# HUD.net
KiCad netlist of a schematic drawn in EAGLE
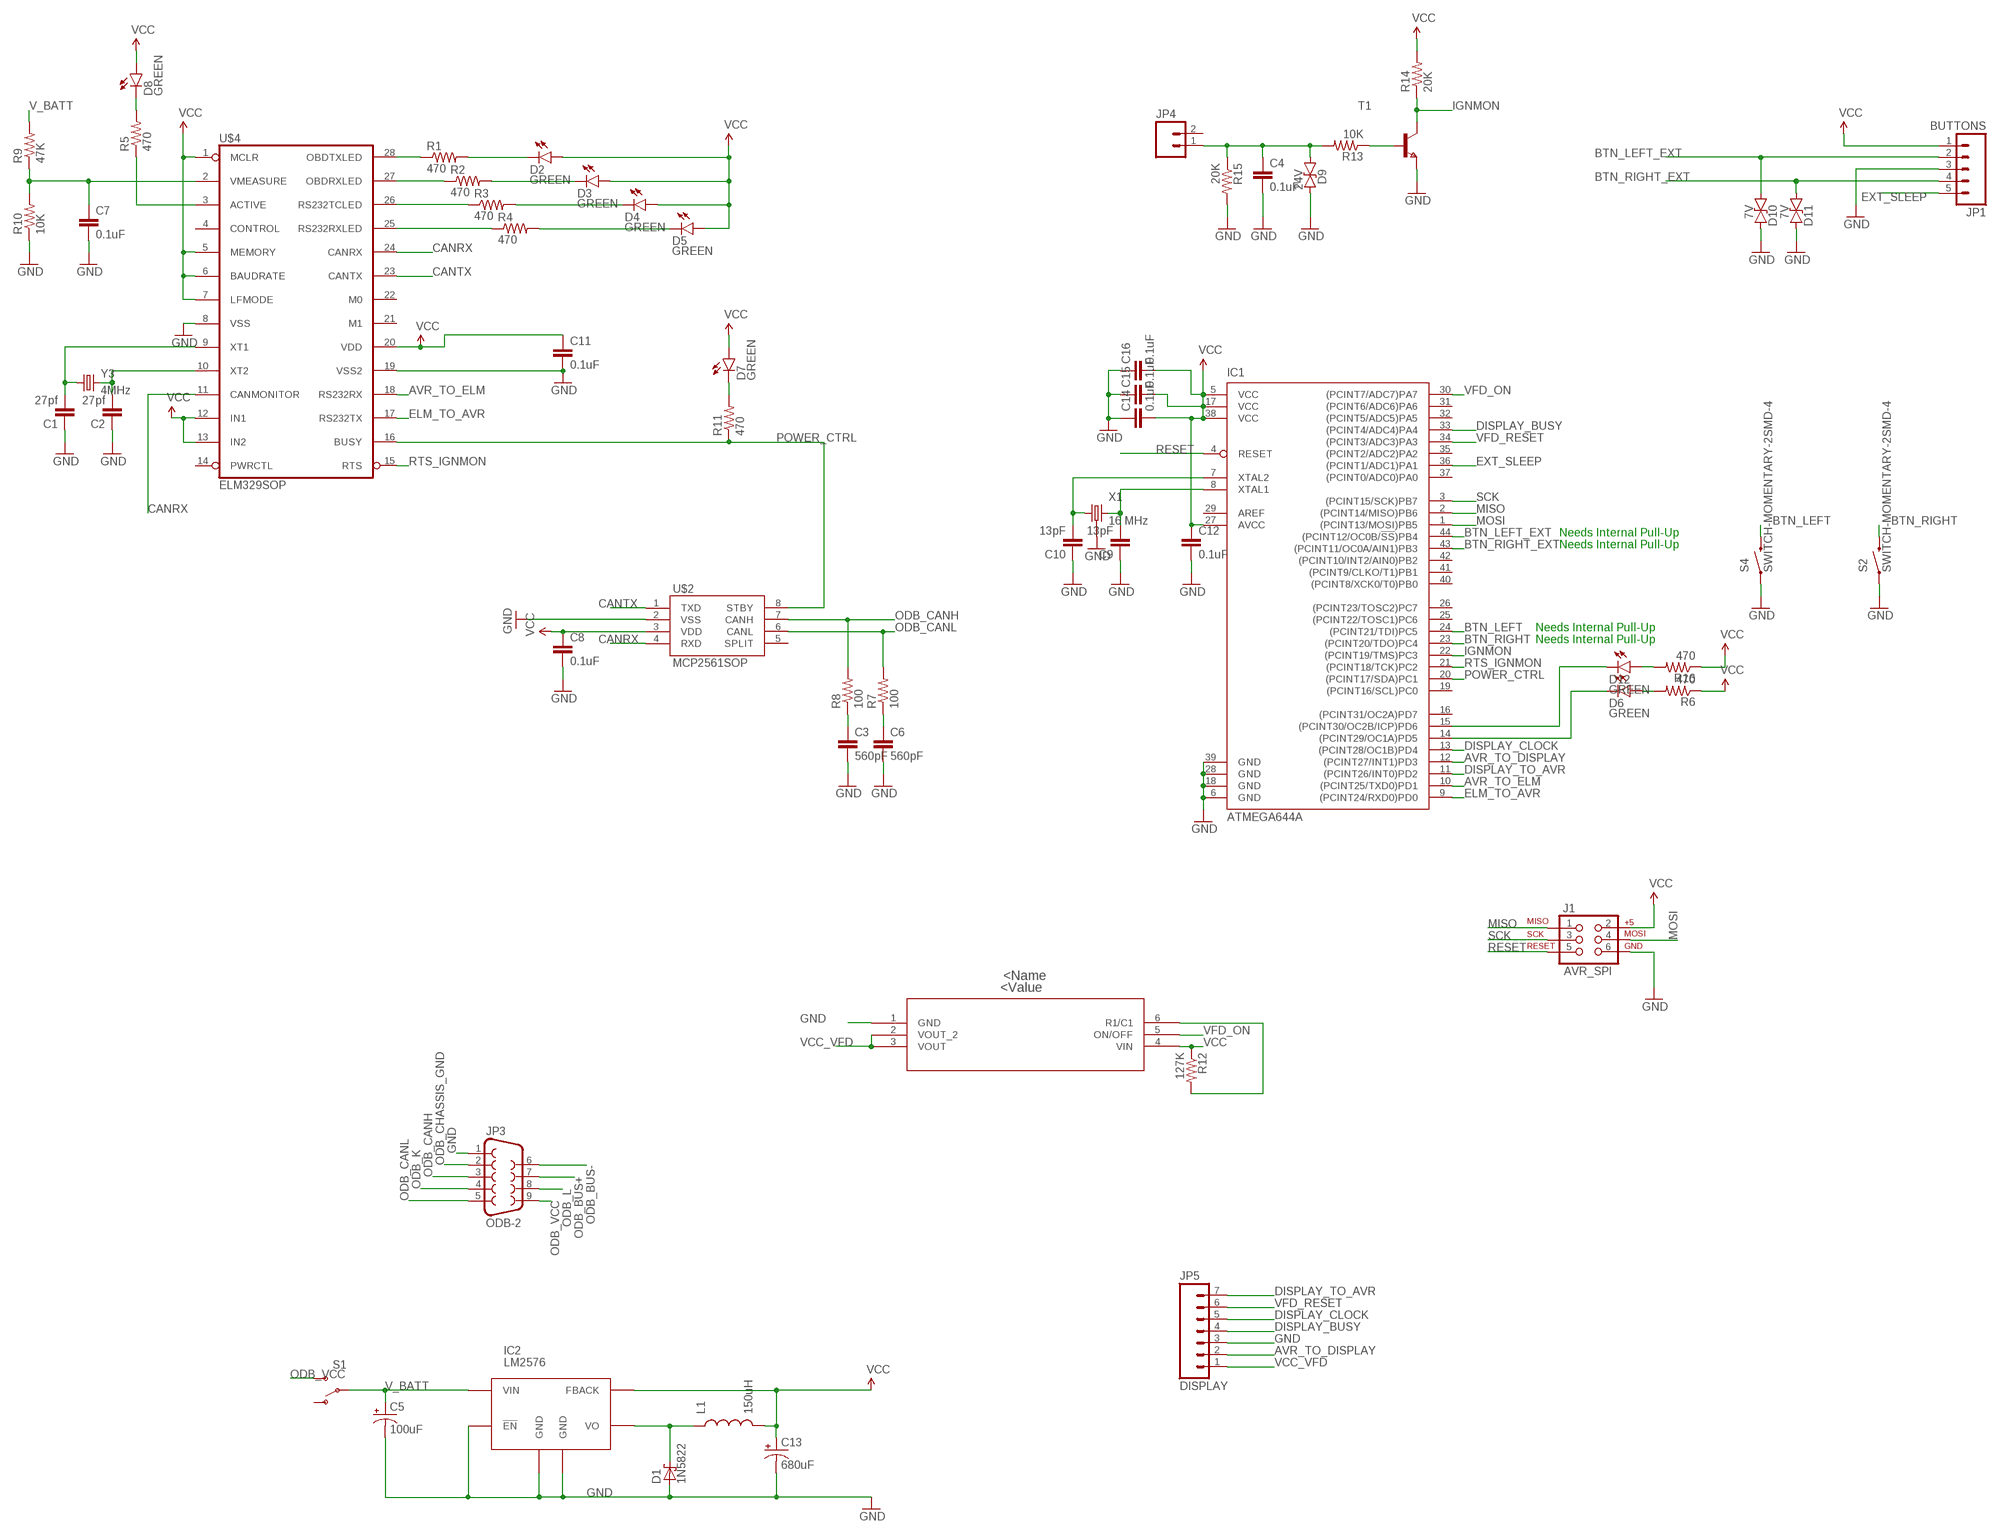
[diagram p0: schematic, sheet 1]

(export (version "E")
  (design (tool "Eeschema 10.0.6"))
  (components
    (comp (ref "C1")
      (value "27pf")
      (footprint "eagle-import:0603-CAP")
      (libsource (lib "eagle-import") (part "560PF-50V-5%(0603)"))
    )
    (comp (ref "C2")
      (value "27pf")
      (footprint "eagle-import:0603-CAP")
      (libsource (lib "eagle-import") (part "560PF-50V-5%(0603)"))
    )
    (comp (ref "C3")
      (value "560pF")
      (footprint "eagle-import:0603-CAP")
      (libsource (lib "eagle-import") (part "560PF-50V-5%(0603)"))
    )
    (comp (ref "C4")
      (value "0.1uF")
      (footprint "eagle-import:0603-CAP")
      (libsource (lib "eagle-import") (part "560PF-50V-5%(0603)"))
    )
    (comp (ref "C5")
      (value "100uF")
      (footprint "eagle-import:CPOL-RADIAL-100UF-25V")
      (libsource (lib "eagle-import") (part "CAP_POLPTH1"))
    )
    (comp (ref "C6")
      (value "560pF")
      (footprint "eagle-import:0603-CAP")
      (libsource (lib "eagle-import") (part "560PF-50V-5%(0603)"))
    )
    (comp (ref "C7")
      (value "0.1uF")
      (footprint "eagle-import:0603-CAP")
      (libsource (lib "eagle-import") (part "560PF-50V-5%(0603)"))
    )
    (comp (ref "C8")
      (value "0.1uF")
      (footprint "eagle-import:0603-CAP")
      (libsource (lib "eagle-import") (part "560PF-50V-5%(0603)"))
    )
    (comp (ref "C9")
      (value "13pF")
      (footprint "eagle-import:0603-CAP")
      (libsource (lib "eagle-import") (part "560PF-50V-5%(0603)"))
    )
    (comp (ref "C10")
      (value "13pF")
      (footprint "eagle-import:0603-CAP")
      (libsource (lib "eagle-import") (part "560PF-50V-5%(0603)"))
    )
    (comp (ref "C11")
      (value "0.1uF")
      (footprint "eagle-import:0603-CAP")
      (libsource (lib "eagle-import") (part "560PF-50V-5%(0603)"))
    )
    (comp (ref "C12")
      (value "0.1uF")
      (footprint "eagle-import:0603-CAP")
      (libsource (lib "eagle-import") (part "560PF-50V-5%(0603)"))
    )
    (comp (ref "C13")
      (value "680uF")
      (footprint "eagle-import:CPOL-RADIAL-1000UF-25V")
      (libsource (lib "eagle-import") (part "1000UF-25V(PTH)"))
    )
    (comp (ref "C14")
      (value "0.1uF")
      (footprint "eagle-import:0603-CAP")
      (libsource (lib "eagle-import") (part "560PF-50V-5%(0603)"))
    )
    (comp (ref "C15")
      (value "0.1uF")
      (footprint "eagle-import:0603-CAP")
      (libsource (lib "eagle-import") (part "560PF-50V-5%(0603)"))
    )
    (comp (ref "C16")
      (value "0.1uF")
      (footprint "eagle-import:0603-CAP")
      (libsource (lib "eagle-import") (part "560PF-50V-5%(0603)"))
    )
    (comp (ref "D1")
      (value "1N5822")
      (footprint "eagle-import:DO201T15")
      (libsource (lib "eagle-import") (part "SCHOTTKY-DIODEDO201T15"))
    )
    (comp (ref "D2")
      (value "GREEN")
      (footprint "eagle-import:LED-1206")
      (libsource (lib "eagle-import") (part "LED-GREENLARGE"))
    )
    (comp (ref "D3")
      (value "GREEN")
      (footprint "eagle-import:LED-1206")
      (libsource (lib "eagle-import") (part "LED-GREENLARGE"))
    )
    (comp (ref "D4")
      (value "GREEN")
      (footprint "eagle-import:LED-1206")
      (libsource (lib "eagle-import") (part "LED-GREENLARGE"))
    )
    (comp (ref "D5")
      (value "GREEN")
      (footprint "eagle-import:LED-1206")
      (libsource (lib "eagle-import") (part "LED-GREENLARGE"))
    )
    (comp (ref "D6")
      (value "GREEN")
      (footprint "eagle-import:LED-1206")
      (libsource (lib "eagle-import") (part "LED-GREENLARGE"))
    )
    (comp (ref "D7")
      (value "GREEN")
      (footprint "eagle-import:LED-1206")
      (libsource (lib "eagle-import") (part "LED-GREENLARGE"))
    )
    (comp (ref "D8")
      (value "GREEN")
      (footprint "eagle-import:LED-1206")
      (libsource (lib "eagle-import") (part "LED-GREENLARGE"))
    )
    (comp (ref "D9")
      (value "24V")
      (footprint "eagle-import:SOD-123")
      (libsource (lib "eagle-import") (part "DIODE-TVS16V"))
    )
    (comp (ref "D10")
      (value "7V")
      (footprint "eagle-import:SOD-123")
      (libsource (lib "eagle-import") (part "DIODE-TVS16V"))
    )
    (comp (ref "D11")
      (value "7V")
      (footprint "eagle-import:SOD-123")
      (libsource (lib "eagle-import") (part "DIODE-TVS16V"))
    )
    (comp (ref "D12")
      (value "GREEN")
      (footprint "eagle-import:LED-1206")
      (libsource (lib "eagle-import") (part "LED-GREENLARGE"))
    )
    (comp (ref "IC1")
      (value "ATMEGA644A")
      (footprint "eagle-import:TQFP44")
      (fields (field (name "MPN") "ATMEGA644PV-10AU"))
      (libsource (lib "eagle-import") (part "ATMEGA644A"))
    )
    (comp (ref "IC2")
      (value "LM2576")
      (footprint "eagle-import:TO263-5")
      (libsource (lib "eagle-import") (part "LM2576S"))
    )
    (comp (ref "J1")
      (value "AVR_SPI")
      (footprint "eagle-import:2X3")
      (libsource (lib "eagle-import") (part "AVR_SPI_PRG_6PTH"))
    )
    (comp (ref "JP1")
      (value "BUTTONS")
      (footprint "eagle-import:1X05_LOCK")
      (libsource (lib "eagle-import") (part "M05LOCK"))
    )
    (comp (ref "JP3")
      (value "ODB-2")
      (footprint "eagle-import:DB9_MALE")
      (libsource (lib "eagle-import") (part "DB9MALE"))
    )
    (comp (ref "JP4")
      (value "M02LOCK")
      (footprint "eagle-import:1X02_LOCK")
      (libsource (lib "eagle-import") (part "M02LOCK"))
    )
    (comp (ref "JP5")
      (value "DISPLAY")
      (footprint "eagle-import:1X07_LOCK")
      (libsource (lib "eagle-import") (part "M07LOCK"))
    )
    (comp (ref "L1")
      (value "150uH")
      (footprint "eagle-import:CDRH125")
      (libsource (lib "eagle-import") (part "INDUCTORPWR"))
    )
    (comp (ref "R1")
      (value "470")
      (footprint "eagle-import:0603-RES")
      (libsource (lib "eagle-import") (part "RESISTOR0603-RES"))
    )
    (comp (ref "R2")
      (value "470")
      (footprint "eagle-import:0603-RES")
      (libsource (lib "eagle-import") (part "RESISTOR0603-RES"))
    )
    (comp (ref "R3")
      (value "470")
      (footprint "eagle-import:0603-RES")
      (libsource (lib "eagle-import") (part "RESISTOR0603-RES"))
    )
    (comp (ref "R4")
      (value "470")
      (footprint "eagle-import:0603-RES")
      (libsource (lib "eagle-import") (part "RESISTOR0603-RES"))
    )
    (comp (ref "R5")
      (value "470")
      (footprint "eagle-import:0603-RES")
      (libsource (lib "eagle-import") (part "RESISTOR0603-RES"))
    )
    (comp (ref "R6")
      (value "470")
      (footprint "eagle-import:0603-RES")
      (libsource (lib "eagle-import") (part "RESISTOR0603-RES"))
    )
    (comp (ref "R7")
      (value "100")
      (footprint "eagle-import:0603-RES")
      (libsource (lib "eagle-import") (part "RESISTOR0603-RES"))
    )
    (comp (ref "R8")
      (value "100")
      (footprint "eagle-import:0603-RES")
      (libsource (lib "eagle-import") (part "RESISTOR0603-RES"))
    )
    (comp (ref "R9")
      (value "47K")
      (footprint "eagle-import:0603-RES")
      (libsource (lib "eagle-import") (part "RESISTOR0603-RES"))
    )
    (comp (ref "R10")
      (value "10K")
      (footprint "eagle-import:0603-RES")
      (libsource (lib "eagle-import") (part "RESISTOR0603-RES"))
    )
    (comp (ref "R11")
      (value "470")
      (footprint "eagle-import:0603-RES")
      (libsource (lib "eagle-import") (part "RESISTOR0603-RES"))
    )
    (comp (ref "R12")
      (value "127K")
      (footprint "eagle-import:0603-RES")
      (libsource (lib "eagle-import") (part "RESISTOR0603-RES"))
    )
    (comp (ref "R13")
      (value "10K")
      (footprint "eagle-import:0603-RES")
      (libsource (lib "eagle-import") (part "RESISTOR0603-RES"))
    )
    (comp (ref "R14")
      (value "20K")
      (footprint "eagle-import:0603-RES")
      (libsource (lib "eagle-import") (part "RESISTOR0603-RES"))
    )
    (comp (ref "R15")
      (value "20K")
      (footprint "eagle-import:0603-RES")
      (libsource (lib "eagle-import") (part "RESISTOR0603-RES"))
    )
    (comp (ref "R16")
      (value "470")
      (footprint "eagle-import:0603-RES")
      (libsource (lib "eagle-import") (part "RESISTOR0603-RES"))
    )
    (comp (ref "S1")
      (value "SWITCH-SPDTPTH")
      (footprint "eagle-import:SWITCH-SPDT")
      (libsource (lib "eagle-import") (part "SWITCH-SPDTPTH"))
    )
    (comp (ref "S2")
      (value "SWITCH-MOMENTARY-2SMD-4")
      (footprint "eagle-import:TACTILE_SWITCH_TALL")
      (libsource (lib "eagle-import") (part "SWITCH-MOMENTARY-2SMD-4"))
    )
    (comp (ref "S4")
      (value "SWITCH-MOMENTARY-2SMD-4")
      (footprint "eagle-import:TACTILE_SWITCH_TALL")
      (libsource (lib "eagle-import") (part "SWITCH-MOMENTARY-2SMD-4"))
    )
    (comp (ref "T1")
      (value "NPNSOT323")
      (footprint "eagle-import:SOT323")
      (fields (field (name "MPN") "DSS4160U-7"))
      (libsource (lib "eagle-import") (part "NPNSOT323"))
    )
    (comp (ref "U$1")
      (value "TPS27082LDDCRDDC6-M")
      (footprint "eagle-import:DDC6-M")
      (fields
        (field (name "MANUFACTURER_PART_NUMBER") "tps27082lddcr")
        (field (name "COPYRIGHT") "Copyright C 2015 Accelerated Designs. All rights reserved")
      )
      (libsource (lib "eagle-import") (part "TPS27082LDDCRDDC6-M"))
    )
    (comp (ref "U$2")
      (value "MCP2561SOP")
      (footprint "eagle-import:SO08")
      (libsource (lib "eagle-import") (part "MCP2561SOP"))
    )
    (comp (ref "U$4")
      (value "ELM329SOP")
      (footprint "eagle-import:SO28W")
      (libsource (lib "eagle-import") (part "ELM329SOP"))
    )
    (comp (ref "X1")
      (value "16 MHz")
      (footprint "eagle-import:CRYSTAL-SMD-3.2X2.5")
      (libsource (lib "eagle-import") (part "CRYSTAL-GROUNDED3.2X2.5"))
    )
    (comp (ref "Y3")
      (value "4MHz")
      (footprint "eagle-import:HC49US")
      (libsource (lib "eagle-import") (part "CRYSTALHC49US"))
    )
  )
  (nets
    (net (code "1") (name "/AVR_TO_DISPLAY") (class "Default")
      (node (ref "IC1") (pin "12") (pinfunction "(PCINT27/INT1)PD3_12") (pintype "bidirectional"))
      (node (ref "JP5") (pin "2") (pinfunction "2_2") (pintype "passive"))
    )
    (net (code "2") (name "/AVR_TO_ELM") (class "Default")
      (node (ref "IC1") (pin "10") (pinfunction "(PCINT25/TXD0)PD1_10") (pintype "bidirectional"))
      (node (ref "U$4") (pin "18") (pinfunction "RS232RX_18") (pintype "bidirectional"))
    )
    (net (code "3") (name "/BTN_LEFT") (class "Default")
      (node (ref "IC1") (pin "24") (pinfunction "(PCINT21/TDI)PC5_24") (pintype "output"))
      (node (ref "S4") (pin "B2") (pinfunction "2_B2") (pintype "passive"))
    )
    (net (code "4") (name "/BTN_LEFT_EXT") (class "Default")
      (node (ref "D10") (pin "A") (pinfunction "A_A") (pintype "passive"))
      (node (ref "IC1") (pin "44") (pinfunction "(PCINT12/OC0B/~{SS})PB4_44") (pintype "bidirectional"))
      (node (ref "JP1") (pin "2") (pinfunction "2_2") (pintype "passive"))
    )
    (net (code "5") (name "/BTN_RIGHT") (class "Default")
      (node (ref "IC1") (pin "23") (pinfunction "(PCINT20/TDO)PC4_23") (pintype "output"))
      (node (ref "S2") (pin "B2") (pinfunction "2_B2") (pintype "passive"))
    )
    (net (code "6") (name "/BTN_RIGHT_EXT") (class "Default")
      (node (ref "D11") (pin "A") (pinfunction "A_A") (pintype "passive"))
      (node (ref "IC1") (pin "43") (pinfunction "(PCINT11/OC0A/AIN1)PB3_43") (pintype "bidirectional"))
      (node (ref "JP1") (pin "4") (pinfunction "4_4") (pintype "passive"))
    )
    (net (code "7") (name "/CANRX") (class "Default")
      (node (ref "U$2") (pin "4") (pinfunction "RXD_4") (pintype "bidirectional"))
      (node (ref "U$4") (pin "11") (pinfunction "CANMONITOR_11") (pintype "bidirectional"))
      (node (ref "U$4") (pin "24") (pinfunction "CANRX_24") (pintype "bidirectional"))
    )
    (net (code "8") (name "/CANTX") (class "Default")
      (node (ref "U$2") (pin "1") (pinfunction "TXD_1") (pintype "bidirectional"))
      (node (ref "U$4") (pin "23") (pinfunction "CANTX_23") (pintype "bidirectional"))
    )
    (net (code "9") (name "/DISPLAY_BUSY") (class "Default")
      (node (ref "IC1") (pin "33") (pinfunction "(PCINT4/ADC4)PA4_33") (pintype "bidirectional"))
      (node (ref "JP5") (pin "4") (pinfunction "4_4") (pintype "passive"))
    )
    (net (code "10") (name "/DISPLAY_CLOCK") (class "Default")
      (node (ref "IC1") (pin "13") (pinfunction "(PCINT28/OC1B)PD4_13") (pintype "bidirectional"))
      (node (ref "JP5") (pin "5") (pinfunction "5_5") (pintype "passive"))
    )
    (net (code "11") (name "/DISPLAY_TO_AVR") (class "Default")
      (node (ref "IC1") (pin "11") (pinfunction "(PCINT26/INT0)PD2_11") (pintype "bidirectional"))
      (node (ref "JP5") (pin "7") (pinfunction "7_7") (pintype "passive"))
    )
    (net (code "12") (name "/ELM_TO_AVR") (class "Default")
      (node (ref "IC1") (pin "9") (pinfunction "(PCINT24/RXD0)PD0_9") (pintype "bidirectional"))
      (node (ref "U$4") (pin "17") (pinfunction "RS232TX_17") (pintype "bidirectional"))
    )
    (net (code "13") (name "/EXT_SLEEP") (class "Default")
      (node (ref "IC1") (pin "36") (pinfunction "(PCINT1/ADC1)PA1_36") (pintype "bidirectional"))
      (node (ref "JP1") (pin "5") (pinfunction "5_5") (pintype "passive"))
    )
    (net (code "14") (name "/IGNMON") (class "Default")
      (node (ref "IC1") (pin "22") (pinfunction "(PCINT19/TMS)PC3_22") (pintype "output"))
      (node (ref "R14") (pin "1") (pinfunction "1_1") (pintype "passive"))
      (node (ref "T1") (pin "1") (pinfunction "C_1") (pintype "passive"))
    )
    (net (code "15") (name "/MISO") (class "Default")
      (node (ref "IC1") (pin "2") (pinfunction "(PCINT14/MISO)PB6_2") (pintype "bidirectional"))
      (node (ref "J1") (pin "1") (pinfunction "1_1") (pintype "passive"))
    )
    (net (code "16") (name "/MOSI") (class "Default")
      (node (ref "IC1") (pin "1") (pinfunction "(PCINT13/MOSI)PB5_1") (pintype "bidirectional"))
      (node (ref "J1") (pin "4") (pinfunction "4_4") (pintype "passive"))
    )
    (net (code "17") (name "/ODB_BUS+") (class "Default")
      (node (ref "JP3") (pin "7") (pinfunction "7_7") (pintype "passive"))
    )
    (net (code "18") (name "/ODB_BUS-") (class "Default")
      (node (ref "JP3") (pin "6") (pinfunction "6_6") (pintype "passive"))
    )
    (net (code "19") (name "/ODB_CANH") (class "Default")
      (node (ref "JP3") (pin "3") (pinfunction "3_3") (pintype "passive"))
      (node (ref "R8") (pin "2") (pinfunction "2_2") (pintype "passive"))
      (node (ref "U$2") (pin "7") (pinfunction "CANH_7") (pintype "bidirectional"))
    )
    (net (code "20") (name "/ODB_CANL") (class "Default")
      (node (ref "JP3") (pin "5") (pinfunction "5_5") (pintype "passive"))
      (node (ref "R7") (pin "2") (pinfunction "2_2") (pintype "passive"))
      (node (ref "U$2") (pin "6") (pinfunction "CANL_6") (pintype "bidirectional"))
    )
    (net (code "21") (name "/ODB_CHASSIS_GND") (class "Default")
      (node (ref "JP3") (pin "2") (pinfunction "2_2") (pintype "passive"))
    )
    (net (code "22") (name "/ODB_K") (class "Default")
      (node (ref "JP3") (pin "4") (pinfunction "4_4") (pintype "passive"))
    )
    (net (code "23") (name "/ODB_L") (class "Default")
      (node (ref "JP3") (pin "8") (pinfunction "8_8") (pintype "passive"))
    )
    (net (code "24") (name "/ODB_VCC") (class "Default")
      (node (ref "JP3") (pin "9") (pinfunction "9_9") (pintype "passive"))
      (node (ref "S1") (pin "3") (pinfunction "S_3") (pintype "passive"))
    )
    (net (code "25") (name "/POWER_CTRL") (class "Default")
      (node (ref "IC1") (pin "20") (pinfunction "(PCINT17/SDA)PC1_20") (pintype "output"))
      (node (ref "R11") (pin "1") (pinfunction "1_1") (pintype "passive"))
      (node (ref "U$2") (pin "8") (pinfunction "STBY_8") (pintype "bidirectional"))
      (node (ref "U$4") (pin "16") (pinfunction "BUSY_16") (pintype "bidirectional"))
    )
    (net (code "26") (name "/RESET") (class "Default")
      (node (ref "IC1") (pin "4") (pinfunction "RESET_4") (pintype "input"))
      (node (ref "J1") (pin "5") (pinfunction "5_5") (pintype "passive"))
    )
    (net (code "27") (name "/RTS_IGNMON") (class "Default")
      (node (ref "IC1") (pin "21") (pinfunction "(PCINT18/TCK)PC2_21") (pintype "output"))
      (node (ref "U$4") (pin "15") (pinfunction "RTS_15") (pintype "bidirectional"))
    )
    (net (code "28") (name "/SCK") (class "Default")
      (node (ref "IC1") (pin "3") (pinfunction "(PCINT15/SCK)PB7_3") (pintype "bidirectional"))
      (node (ref "J1") (pin "3") (pinfunction "3_3") (pintype "passive"))
    )
    (net (code "29") (name "/VCC_VFD") (class "Default")
      (node (ref "JP5") (pin "1") (pinfunction "1_1") (pintype "passive"))
      (node (ref "U$1") (pin "2") (pinfunction "VOUT_2_2") (pintype "output"))
      (node (ref "U$1") (pin "3") (pinfunction "VOUT_3") (pintype "output"))
    )
    (net (code "30") (name "/VFD_ON") (class "Default")
      (node (ref "IC1") (pin "30") (pinfunction "(PCINT7/ADC7)PA7_30") (pintype "bidirectional"))
      (node (ref "U$1") (pin "5") (pinfunction "ON/OFF_5") (pintype "passive"))
    )
    (net (code "31") (name "/VFD_RESET") (class "Default")
      (node (ref "IC1") (pin "34") (pinfunction "(PCINT3/ADC3)PA3_34") (pintype "bidirectional"))
      (node (ref "JP5") (pin "6") (pinfunction "6_6") (pintype "passive"))
    )
    (net (code "32") (name "/V_BATT") (class "Default")
      (node (ref "C5") (pin "1") (pinfunction "+_1") (pintype "passive"))
      (node (ref "IC2") (pin "1") (pinfunction "VIN_1") (pintype "bidirectional"))
      (node (ref "R9") (pin "2") (pinfunction "2_2") (pintype "passive"))
      (node (ref "S1") (pin "2") (pinfunction "P_2") (pintype "passive"))
    )
    (net (code "33") (name "GND") (class "Default")
      (node (ref "C1") (pin "1") (pinfunction "1_1") (pintype "passive"))
      (node (ref "C10") (pin "1") (pinfunction "1_1") (pintype "passive"))
      (node (ref "C11") (pin "2") (pinfunction "2_2") (pintype "passive"))
      (node (ref "C12") (pin "2") (pinfunction "2_2") (pintype "passive"))
      (node (ref "C13") (pin "-") (pinfunction "-_-") (pintype "passive"))
      (node (ref "C14") (pin "1") (pinfunction "1_1") (pintype "passive"))
      (node (ref "C15") (pin "1") (pinfunction "1_1") (pintype "passive"))
      (node (ref "C16") (pin "1") (pinfunction "1_1") (pintype "passive"))
      (node (ref "C2") (pin "1") (pinfunction "1_1") (pintype "passive"))
      (node (ref "C3") (pin "2") (pinfunction "2_2") (pintype "passive"))
      (node (ref "C4") (pin "2") (pinfunction "2_2") (pintype "passive"))
      (node (ref "C5") (pin "2") (pinfunction "-_2") (pintype "passive"))
      (node (ref "C6") (pin "2") (pinfunction "2_2") (pintype "passive"))
      (node (ref "C7") (pin "2") (pinfunction "2_2") (pintype "passive"))
      (node (ref "C8") (pin "2") (pinfunction "2_2") (pintype "passive"))
      (node (ref "C9") (pin "1") (pinfunction "1_1") (pintype "passive"))
      (node (ref "D1") (pin "A") (pinfunction "A_A") (pintype "passive"))
      (node (ref "D10") (pin "C") (pinfunction "C_C") (pintype "passive"))
      (node (ref "D11") (pin "C") (pinfunction "C_C") (pintype "passive"))
      (node (ref "D9") (pin "C") (pinfunction "C_C") (pintype "passive"))
      (node (ref "IC1") (pin "18") (pinfunction "GND_18") (pintype "power_in"))
      (node (ref "IC1") (pin "28") (pinfunction "GND_28") (pintype "power_in"))
      (node (ref "IC1") (pin "39") (pinfunction "GND_39") (pintype "power_in"))
      (node (ref "IC1") (pin "6") (pinfunction "GND_6") (pintype "power_in"))
      (node (ref "IC2") (pin "3") (pinfunction "GND_3") (pintype "bidirectional"))
      (node (ref "IC2") (pin "5") (pinfunction "~{EN}_5") (pintype "bidirectional"))
      (node (ref "IC2") (pin "TAB") (pinfunction "GND_TAB") (pintype "bidirectional"))
      (node (ref "J1") (pin "6") (pinfunction "6_6") (pintype "passive"))
      (node (ref "JP1") (pin "3") (pinfunction "3_3") (pintype "passive"))
      (node (ref "JP3") (pin "1") (pinfunction "1_1") (pintype "passive"))
      (node (ref "JP5") (pin "3") (pinfunction "3_3") (pintype "passive"))
      (node (ref "R10") (pin "1") (pinfunction "1_1") (pintype "passive"))
      (node (ref "R15") (pin "2") (pinfunction "2_2") (pintype "passive"))
      (node (ref "S2") (pin "A2") (pinfunction "1_A2") (pintype "passive"))
      (node (ref "S4") (pin "A2") (pinfunction "1_A2") (pintype "passive"))
      (node (ref "T1") (pin "3") (pinfunction "E_3") (pintype "passive"))
      (node (ref "U$1") (pin "1") (pinfunction "GND_1") (pintype "power_in"))
      (node (ref "U$2") (pin "2") (pinfunction "VSS_2") (pintype "bidirectional"))
      (node (ref "U$4") (pin "19") (pinfunction "VSS2_19") (pintype "bidirectional"))
      (node (ref "U$4") (pin "8") (pinfunction "VSS_8") (pintype "bidirectional"))
      (node (ref "X1") (pin "2") (pinfunction "3_2") (pintype "passive"))
      (node (ref "X1") (pin "4") (pinfunction "3_4") (pintype "passive"))
    )
    (net (code "34") (name "Net-(C3-Pad1)") (class "Default")
      (node (ref "C3") (pin "1") (pinfunction "1_1") (pintype "passive"))
      (node (ref "R8") (pin "1") (pinfunction "1_1") (pintype "passive"))
    )
    (net (code "35") (name "Net-(C4-Pad1)") (class "Default")
      (node (ref "C4") (pin "1") (pinfunction "1_1") (pintype "passive"))
      (node (ref "D9") (pin "A") (pinfunction "A_A") (pintype "passive"))
      (node (ref "JP4") (pin "1") (pinfunction "1_1") (pintype "passive"))
      (node (ref "R13") (pin "2") (pinfunction "2_2") (pintype "passive"))
      (node (ref "R15") (pin "1") (pinfunction "1_1") (pintype "passive"))
    )
    (net (code "36") (name "Net-(C6-Pad1)") (class "Default")
      (node (ref "C6") (pin "1") (pinfunction "1_1") (pintype "passive"))
      (node (ref "R7") (pin "1") (pinfunction "1_1") (pintype "passive"))
    )
    (net (code "37") (name "Net-(D2-PadC)") (class "Default")
      (node (ref "D2") (pin "C") (pinfunction "C_C") (pintype "passive"))
      (node (ref "R1") (pin "2") (pinfunction "2_2") (pintype "passive"))
    )
    (net (code "38") (name "Net-(D3-PadC)") (class "Default")
      (node (ref "D3") (pin "C") (pinfunction "C_C") (pintype "passive"))
      (node (ref "R2") (pin "2") (pinfunction "2_2") (pintype "passive"))
    )
    (net (code "39") (name "Net-(D4-PadC)") (class "Default")
      (node (ref "D4") (pin "C") (pinfunction "C_C") (pintype "passive"))
      (node (ref "R3") (pin "2") (pinfunction "2_2") (pintype "passive"))
    )
    (net (code "40") (name "Net-(D5-PadC)") (class "Default")
      (node (ref "D5") (pin "C") (pinfunction "C_C") (pintype "passive"))
      (node (ref "R4") (pin "2") (pinfunction "2_2") (pintype "passive"))
    )
    (net (code "41") (name "Net-(D6-PadA)") (class "Default")
      (node (ref "D6") (pin "A") (pinfunction "A_A") (pintype "passive"))
      (node (ref "R6") (pin "2") (pinfunction "2_2") (pintype "passive"))
    )
    (net (code "42") (name "Net-(D7-PadC)") (class "Default")
      (node (ref "D7") (pin "C") (pinfunction "C_C") (pintype "passive"))
      (node (ref "R11") (pin "2") (pinfunction "2_2") (pintype "passive"))
    )
    (net (code "43") (name "Net-(D8-PadC)") (class "Default")
      (node (ref "D8") (pin "C") (pinfunction "C_C") (pintype "passive"))
      (node (ref "R5") (pin "2") (pinfunction "2_2") (pintype "passive"))
    )
    (net (code "44") (name "Net-(D12-PadA)") (class "Default")
      (node (ref "D12") (pin "A") (pinfunction "A_A") (pintype "passive"))
      (node (ref "R16") (pin "2") (pinfunction "2_2") (pintype "passive"))
    )
    (net (code "45") (name "Net-(IC1-(PCINT29{slash}OC1A)PD5)") (class "Default")
      (node (ref "D6") (pin "C") (pinfunction "C_C") (pintype "passive"))
      (node (ref "IC1") (pin "14") (pinfunction "(PCINT29/OC1A)PD5_14") (pintype "bidirectional"))
    )
    (net (code "46") (name "Net-(IC1-(PCINT30{slash}OC2B{slash}ICP)PD6)") (class "Default")
      (node (ref "D12") (pin "C") (pinfunction "C_C") (pintype "passive"))
      (node (ref "IC1") (pin "15") (pinfunction "(PCINT30/OC2B/ICP)PD6_15") (pintype "bidirectional"))
    )
    (net (code "47") (name "Net-(IC1-XTAL1)") (class "Default")
      (node (ref "C9") (pin "2") (pinfunction "2_2") (pintype "passive"))
      (node (ref "IC1") (pin "8") (pinfunction "XTAL1_8") (pintype "bidirectional"))
      (node (ref "X1") (pin "1") (pinfunction "2_1") (pintype "passive"))
    )
    (net (code "48") (name "Net-(IC1-XTAL2)") (class "Default")
      (node (ref "C10") (pin "2") (pinfunction "2_2") (pintype "passive"))
      (node (ref "IC1") (pin "7") (pinfunction "XTAL2_7") (pintype "bidirectional"))
      (node (ref "X1") (pin "3") (pinfunction "1_3") (pintype "passive"))
    )
    (net (code "49") (name "Net-(IC2-VO)") (class "Default")
      (node (ref "D1") (pin "C") (pinfunction "C_C") (pintype "passive"))
      (node (ref "IC2") (pin "2") (pinfunction "VO_2") (pintype "bidirectional"))
      (node (ref "L1") (pin "1") (pinfunction "1_1") (pintype "passive"))
    )
    (net (code "50") (name "Net-(T1-B)") (class "Default")
      (node (ref "R13") (pin "1") (pinfunction "1_1") (pintype "passive"))
      (node (ref "T1") (pin "2") (pinfunction "B_2") (pintype "passive"))
    )
    (net (code "51") (name "Net-(U$1-R1{slash}C1)") (class "Default")
      (node (ref "R12") (pin "2") (pinfunction "2_2") (pintype "passive"))
      (node (ref "U$1") (pin "6") (pinfunction "R1/C1_6") (pintype "passive"))
    )
    (net (code "52") (name "Net-(U$4-ACTIVE)") (class "Default")
      (node (ref "R5") (pin "1") (pinfunction "1_1") (pintype "passive"))
      (node (ref "U$4") (pin "3") (pinfunction "ACTIVE_3") (pintype "output"))
    )
    (net (code "53") (name "Net-(U$4-OBDRXLED)") (class "Default")
      (node (ref "R2") (pin "1") (pinfunction "1_1") (pintype "passive"))
      (node (ref "U$4") (pin "27") (pinfunction "OBDRXLED_27") (pintype "bidirectional"))
    )
    (net (code "54") (name "Net-(U$4-OBDTXLED)") (class "Default")
      (node (ref "R1") (pin "1") (pinfunction "1_1") (pintype "passive"))
      (node (ref "U$4") (pin "28") (pinfunction "OBDTXLED_28") (pintype "bidirectional"))
    )
    (net (code "55") (name "Net-(U$4-RS232RXLED)") (class "Default")
      (node (ref "R4") (pin "1") (pinfunction "1_1") (pintype "passive"))
      (node (ref "U$4") (pin "25") (pinfunction "RS232RXLED_25") (pintype "bidirectional"))
    )
    (net (code "56") (name "Net-(U$4-RS232TCLED)") (class "Default")
      (node (ref "R3") (pin "1") (pinfunction "1_1") (pintype "passive"))
      (node (ref "U$4") (pin "26") (pinfunction "RS232TCLED_26") (pintype "bidirectional"))
    )
    (net (code "57") (name "Net-(U$4-VMEASURE)") (class "Default")
      (node (ref "C7") (pin "1") (pinfunction "1_1") (pintype "passive"))
      (node (ref "R10") (pin "2") (pinfunction "2_2") (pintype "passive"))
      (node (ref "R9") (pin "1") (pinfunction "1_1") (pintype "passive"))
      (node (ref "U$4") (pin "2") (pinfunction "VMEASURE_2") (pintype "bidirectional"))
    )
    (net (code "58") (name "Net-(U$4-XT1)") (class "Default")
      (node (ref "C1") (pin "2") (pinfunction "2_2") (pintype "passive"))
      (node (ref "U$4") (pin "9") (pinfunction "XT1_9") (pintype "bidirectional"))
      (node (ref "Y3") (pin "1") (pinfunction "1_1") (pintype "passive"))
    )
    (net (code "59") (name "Net-(U$4-XT2)") (class "Default")
      (node (ref "C2") (pin "2") (pinfunction "2_2") (pintype "passive"))
      (node (ref "U$4") (pin "10") (pinfunction "XT2_10") (pintype "bidirectional"))
      (node (ref "Y3") (pin "2") (pinfunction "2_2") (pintype "passive"))
    )
    (net (code "60") (name "VCC") (class "Default")
      (node (ref "C11") (pin "1") (pinfunction "1_1") (pintype "passive"))
      (node (ref "C12") (pin "1") (pinfunction "1_1") (pintype "passive"))
      (node (ref "C13") (pin "+") (pinfunction "+_+") (pintype "passive"))
      (node (ref "C14") (pin "2") (pinfunction "2_2") (pintype "passive"))
      (node (ref "C15") (pin "2") (pinfunction "2_2") (pintype "passive"))
      (node (ref "C16") (pin "2") (pinfunction "2_2") (pintype "passive"))
      (node (ref "C8") (pin "1") (pinfunction "1_1") (pintype "passive"))
      (node (ref "D2") (pin "A") (pinfunction "A_A") (pintype "passive"))
      (node (ref "D3") (pin "A") (pinfunction "A_A") (pintype "passive"))
      (node (ref "D4") (pin "A") (pinfunction "A_A") (pintype "passive"))
      (node (ref "D5") (pin "A") (pinfunction "A_A") (pintype "passive"))
      (node (ref "D7") (pin "A") (pinfunction "A_A") (pintype "passive"))
      (node (ref "D8") (pin "A") (pinfunction "A_A") (pintype "passive"))
      (node (ref "IC1") (pin "17") (pinfunction "VCC_17") (pintype "power_in"))
      (node (ref "IC1") (pin "27") (pinfunction "AVCC_27") (pintype "power_in"))
      (node (ref "IC1") (pin "38") (pinfunction "VCC_38") (pintype "power_in"))
      (node (ref "IC1") (pin "5") (pinfunction "VCC_5") (pintype "power_in"))
      (node (ref "IC2") (pin "4") (pinfunction "FBACK_4") (pintype "bidirectional"))
      (node (ref "J1") (pin "2") (pinfunction "2_2") (pintype "passive"))
      (node (ref "JP1") (pin "1") (pinfunction "1_1") (pintype "passive"))
      (node (ref "L1") (pin "2") (pinfunction "2_2") (pintype "passive"))
      (node (ref "R12") (pin "1") (pinfunction "1_1") (pintype "passive"))
      (node (ref "R14") (pin "2") (pinfunction "2_2") (pintype "passive"))
      (node (ref "R16") (pin "1") (pinfunction "1_1") (pintype "passive"))
      (node (ref "R6") (pin "1") (pinfunction "1_1") (pintype "passive"))
      (node (ref "U$1") (pin "4") (pinfunction "VIN_4") (pintype "input"))
      (node (ref "U$2") (pin "3") (pinfunction "VDD_3") (pintype "bidirectional"))
      (node (ref "U$4") (pin "1") (pinfunction "MCLR_1") (pintype "bidirectional"))
      (node (ref "U$4") (pin "12") (pinfunction "IN1_12") (pintype "input"))
      (node (ref "U$4") (pin "13") (pinfunction "IN2_13") (pintype "input"))
      (node (ref "U$4") (pin "20") (pinfunction "VDD_20") (pintype "bidirectional"))
      (node (ref "U$4") (pin "5") (pinfunction "MEMORY_5") (pintype "bidirectional"))
      (node (ref "U$4") (pin "6") (pinfunction "BAUDRATE_6") (pintype "bidirectional"))
      (node (ref "U$4") (pin "7") (pinfunction "LFMODE_7") (pintype "bidirectional"))
    )
    (net (code "61") (name "unconnected-(IC1-(PCINT0{slash}ADC0)PA0-Pad37)") (class "Default")
      (node (ref "IC1") (pin "37") (pinfunction "(PCINT0/ADC0)PA0_37") (pintype "bidirectional"))
    )
    (net (code "62") (name "unconnected-(IC1-(PCINT2{slash}ADC2)PA2-Pad35)") (class "Default")
      (node (ref "IC1") (pin "35") (pinfunction "(PCINT2/ADC2)PA2_35") (pintype "bidirectional"))
    )
    (net (code "63") (name "unconnected-(IC1-(PCINT5{slash}ADC5)PA5-Pad32)") (class "Default")
      (node (ref "IC1") (pin "32") (pinfunction "(PCINT5/ADC5)PA5_32") (pintype "bidirectional"))
    )
    (net (code "64") (name "unconnected-(IC1-(PCINT6{slash}ADC6)PA6-Pad31)") (class "Default")
      (node (ref "IC1") (pin "31") (pinfunction "(PCINT6/ADC6)PA6_31") (pintype "bidirectional"))
    )
    (net (code "65") (name "unconnected-(IC1-(PCINT8{slash}XCK0{slash}T0)PB0-Pad40)") (class "Default")
      (node (ref "IC1") (pin "40") (pinfunction "(PCINT8/XCK0/T0)PB0_40") (pintype "bidirectional"))
    )
    (net (code "66") (name "unconnected-(IC1-(PCINT9{slash}CLKO{slash}T1)PB1-Pad41)") (class "Default")
      (node (ref "IC1") (pin "41") (pinfunction "(PCINT9/CLKO/T1)PB1_41") (pintype "bidirectional"))
    )
    (net (code "67") (name "unconnected-(IC1-(PCINT10{slash}INT2{slash}AIN0)PB2-Pad42)") (class "Default")
      (node (ref "IC1") (pin "42") (pinfunction "(PCINT10/INT2/AIN0)PB2_42") (pintype "bidirectional"))
    )
    (net (code "68") (name "unconnected-(IC1-(PCINT16{slash}SCL)PC0-Pad19)") (class "Default")
      (node (ref "IC1") (pin "19") (pinfunction "(PCINT16/SCL)PC0_19") (pintype "output"))
    )
    (net (code "69") (name "unconnected-(IC1-(PCINT22{slash}TOSC1)PC6-Pad25)") (class "Default")
      (node (ref "IC1") (pin "25") (pinfunction "(PCINT22/TOSC1)PC6_25") (pintype "output"))
    )
    (net (code "70") (name "unconnected-(IC1-(PCINT23{slash}TOSC2)PC7-Pad26)") (class "Default")
      (node (ref "IC1") (pin "26") (pinfunction "(PCINT23/TOSC2)PC7_26") (pintype "output"))
    )
    (net (code "71") (name "unconnected-(IC1-(PCINT31{slash}OC2A)PD7-Pad16)") (class "Default")
      (node (ref "IC1") (pin "16") (pinfunction "(PCINT31/OC2A)PD7_16") (pintype "bidirectional"))
    )
    (net (code "72") (name "unconnected-(IC1-AREF-Pad29)") (class "Default")
      (node (ref "IC1") (pin "29") (pinfunction "AREF_29") (pintype "passive"))
    )
    (net (code "73") (name "unconnected-(JP4-Pad2)") (class "Default")
      (node (ref "JP4") (pin "2") (pinfunction "2_2") (pintype "passive"))
    )
    (net (code "74") (name "unconnected-(S1-O-Pad1)") (class "Default")
      (node (ref "S1") (pin "1") (pinfunction "O_1") (pintype "passive"))
    )
    (net (code "75") (name "unconnected-(U$2-SPLIT-Pad5)") (class "Default")
      (node (ref "U$2") (pin "5") (pinfunction "SPLIT_5") (pintype "bidirectional"))
    )
    (net (code "76") (name "unconnected-(U$4-CONTROL-Pad4)") (class "Default")
      (node (ref "U$4") (pin "4") (pinfunction "CONTROL_4") (pintype "output"))
    )
    (net (code "77") (name "unconnected-(U$4-M0-Pad22)") (class "Default")
      (node (ref "U$4") (pin "22") (pinfunction "M0_22") (pintype "output"))
    )
    (net (code "78") (name "unconnected-(U$4-M1-Pad21)") (class "Default")
      (node (ref "U$4") (pin "21") (pinfunction "M1_21") (pintype "output"))
    )
    (net (code "79") (name "unconnected-(U$4-PWRCTL-Pad14)") (class "Default")
      (node (ref "U$4") (pin "14") (pinfunction "PWRCTL_14") (pintype "bidirectional"))
    )
  )
)
